# mb.net
KiCad netlist of a schematic drawn in EAGLE
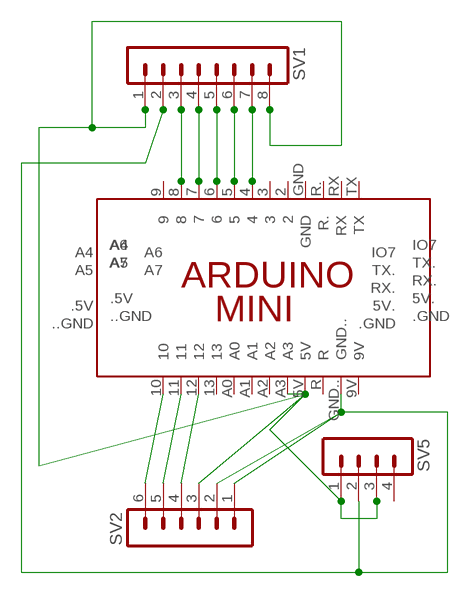
[diagram p0: schematic, sheet 1]

(export (version "E")
  (design (tool "Eeschema 10.0.6"))
  (components
    (comp (ref "PCB2")
      (value "ARDUINO_MINI")
      (footprint "eagle-import:ARDUINO_MINI")
      (libsource (lib "eagle-import") (part "ARDUINO_MINI"))
    )
    (comp (ref "SV1")
      (value "MA08-1W")
      (footprint "eagle-import:MA08-1W")
      (libsource (lib "eagle-import") (part "MA08-1W"))
    )
    (comp (ref "SV2")
      (value "MA06-1")
      (footprint "eagle-import:MA06-1")
      (libsource (lib "eagle-import") (part "MA06-1"))
    )
    (comp (ref "SV5")
      (value "MA04-1")
      (footprint "eagle-import:MA04-1")
      (libsource (lib "eagle-import") (part "MA04-1"))
    )
  )
  (nets
    (net (code "1") (name "Net-(PCB2-Pad4)") (class "Default")
      (node (ref "PCB2") (pin "4") (pinfunction "4_4") (pintype "bidirectional"))
      (node (ref "SV1") (pin "7") (pinfunction "7_7") (pintype "passive"))
    )
    (net (code "2") (name "Net-(PCB2-Pad5)") (class "Default")
      (node (ref "PCB2") (pin "5") (pinfunction "5_5") (pintype "bidirectional"))
      (node (ref "SV1") (pin "6") (pinfunction "6_6") (pintype "passive"))
    )
    (net (code "3") (name "Net-(PCB2-Pad5V)") (class "Default")
      (node (ref "PCB2") (pin "5V") (pinfunction "5V_5V") (pintype "bidirectional"))
      (node (ref "PCB2") (pin "A3") (pinfunction "A3_A3") (pintype "bidirectional"))
      (node (ref "SV1") (pin "1") (pinfunction "1_1") (pintype "passive"))
      (node (ref "SV1") (pin "8") (pinfunction "8_8") (pintype "passive"))
      (node (ref "SV2") (pin "3") (pinfunction "3_3") (pintype "passive"))
      (node (ref "SV5") (pin "1") (pinfunction "1_1") (pintype "passive"))
      (node (ref "SV5") (pin "3") (pinfunction "3_3") (pintype "passive"))
    )
    (net (code "4") (name "Net-(PCB2-Pad6)") (class "Default")
      (node (ref "PCB2") (pin "6") (pinfunction "6_6") (pintype "bidirectional"))
      (node (ref "SV1") (pin "5") (pinfunction "5_5") (pintype "passive"))
    )
    (net (code "5") (name "Net-(PCB2-Pad7)") (class "Default")
      (node (ref "PCB2") (pin "7") (pinfunction "7_7") (pintype "bidirectional"))
      (node (ref "SV1") (pin "4") (pinfunction "4_4") (pintype "passive"))
    )
    (net (code "6") (name "Net-(PCB2-Pad8)") (class "Default")
      (node (ref "PCB2") (pin "8") (pinfunction "8_8") (pintype "bidirectional"))
      (node (ref "SV1") (pin "3") (pinfunction "3_3") (pintype "passive"))
    )
    (net (code "7") (name "Net-(PCB2-Pad10)") (class "Default")
      (node (ref "PCB2") (pin "10") (pinfunction "10_10") (pintype "bidirectional"))
      (node (ref "SV2") (pin "6") (pinfunction "6_6") (pintype "passive"))
    )
    (net (code "8") (name "Net-(PCB2-Pad11)") (class "Default")
      (node (ref "PCB2") (pin "11") (pinfunction "11_11") (pintype "bidirectional"))
      (node (ref "SV2") (pin "5") (pinfunction "5_5") (pintype "passive"))
    )
    (net (code "9") (name "Net-(PCB2-Pad12)") (class "Default")
      (node (ref "PCB2") (pin "12") (pinfunction "12_12") (pintype "bidirectional"))
      (node (ref "SV2") (pin "4") (pinfunction "4_4") (pintype "passive"))
    )
    (net (code "10") (name "Net-(PCB2-PadGND..)") (class "Default")
      (node (ref "PCB2") (pin "GND..") (pinfunction "GND.._GND..") (pintype "bidirectional"))
      (node (ref "SV1") (pin "2") (pinfunction "2_2") (pintype "passive"))
      (node (ref "SV2") (pin "1") (pinfunction "1_1") (pintype "passive"))
      (node (ref "SV2") (pin "2") (pinfunction "2_2") (pintype "passive"))
      (node (ref "SV5") (pin "2") (pinfunction "2_2") (pintype "passive"))
    )
    (net (code "11") (name "unconnected-(PCB2-Pad..GND)") (class "Default")
      (node (ref "PCB2") (pin "..GND") (pinfunction "..GND_..GND") (pintype "bidirectional"))
    )
    (net (code "12") (name "unconnected-(PCB2-Pad.5V)") (class "Default")
      (node (ref "PCB2") (pin ".5V") (pinfunction ".5V_.5V") (pintype "bidirectional"))
    )
    (net (code "13") (name "unconnected-(PCB2-Pad.GND)") (class "Default")
      (node (ref "PCB2") (pin ".GND") (pinfunction ".GND_.GND") (pintype "bidirectional"))
    )
    (net (code "14") (name "unconnected-(PCB2-Pad2)") (class "Default")
      (node (ref "PCB2") (pin "2") (pinfunction "2_2") (pintype "bidirectional"))
    )
    (net (code "15") (name "unconnected-(PCB2-Pad3)") (class "Default")
      (node (ref "PCB2") (pin "3") (pinfunction "3_3") (pintype "bidirectional"))
    )
    (net (code "16") (name "unconnected-(PCB2-Pad5V.)") (class "Default")
      (node (ref "PCB2") (pin "5V.") (pinfunction "5V._5V.") (pintype "bidirectional"))
    )
    (net (code "17") (name "unconnected-(PCB2-Pad9)") (class "Default")
      (node (ref "PCB2") (pin "9") (pinfunction "9_9") (pintype "bidirectional"))
    )
    (net (code "18") (name "unconnected-(PCB2-Pad9V)") (class "Default")
      (node (ref "PCB2") (pin "9V") (pinfunction "9V_9V") (pintype "bidirectional"))
    )
    (net (code "19") (name "unconnected-(PCB2-Pad13)") (class "Default")
      (node (ref "PCB2") (pin "13") (pinfunction "13_13") (pintype "bidirectional"))
    )
    (net (code "20") (name "unconnected-(PCB2-PadA0)") (class "Default")
      (node (ref "PCB2") (pin "A0") (pinfunction "A0_A0") (pintype "bidirectional"))
    )
    (net (code "21") (name "unconnected-(PCB2-PadA1)") (class "Default")
      (node (ref "PCB2") (pin "A1") (pinfunction "A1_A1") (pintype "bidirectional"))
    )
    (net (code "22") (name "unconnected-(PCB2-PadA2)") (class "Default")
      (node (ref "PCB2") (pin "A2") (pinfunction "A2_A2") (pintype "bidirectional"))
    )
    (net (code "23") (name "unconnected-(PCB2-PadA4)") (class "Default")
      (node (ref "PCB2") (pin "A4") (pinfunction "A4_A4") (pintype "bidirectional"))
    )
    (net (code "24") (name "unconnected-(PCB2-PadA5)") (class "Default")
      (node (ref "PCB2") (pin "A5") (pinfunction "A5_A5") (pintype "bidirectional"))
    )
    (net (code "25") (name "unconnected-(PCB2-PadA6)") (class "Default")
      (node (ref "PCB2") (pin "A6") (pinfunction "A6_A6") (pintype "bidirectional"))
    )
    (net (code "26") (name "unconnected-(PCB2-PadA7)") (class "Default")
      (node (ref "PCB2") (pin "A7") (pinfunction "A7_A7") (pintype "bidirectional"))
    )
    (net (code "27") (name "unconnected-(PCB2-PadGND)") (class "Default")
      (node (ref "PCB2") (pin "GND") (pinfunction "GND_GND") (pintype "bidirectional"))
    )
    (net (code "28") (name "unconnected-(PCB2-PadIO7)") (class "Default")
      (node (ref "PCB2") (pin "IO7") (pinfunction "IO7_IO7") (pintype "bidirectional"))
    )
    (net (code "29") (name "unconnected-(PCB2-PadR)") (class "Default")
      (node (ref "PCB2") (pin "R") (pinfunction "R_R") (pintype "bidirectional"))
    )
    (net (code "30") (name "unconnected-(PCB2-PadR.)") (class "Default")
      (node (ref "PCB2") (pin "R.") (pinfunction "R._R.") (pintype "bidirectional"))
    )
    (net (code "31") (name "unconnected-(PCB2-PadRX)") (class "Default")
      (node (ref "PCB2") (pin "RX") (pinfunction "RX_RX") (pintype "bidirectional"))
    )
    (net (code "32") (name "unconnected-(PCB2-PadRX.)") (class "Default")
      (node (ref "PCB2") (pin "RX.") (pinfunction "RX._RX.") (pintype "bidirectional"))
    )
    (net (code "33") (name "unconnected-(PCB2-PadTX)") (class "Default")
      (node (ref "PCB2") (pin "TX") (pinfunction "TX_TX") (pintype "bidirectional"))
    )
    (net (code "34") (name "unconnected-(PCB2-PadTX.)") (class "Default")
      (node (ref "PCB2") (pin "TX.") (pinfunction "TX._TX.") (pintype "bidirectional"))
    )
    (net (code "35") (name "unconnected-(SV5-Pad4)") (class "Default")
      (node (ref "SV5") (pin "4") (pinfunction "4_4") (pintype "passive"))
    )
  )
)
